# Triac.net
KiCad netlist of a schematic drawn in Altium Designer
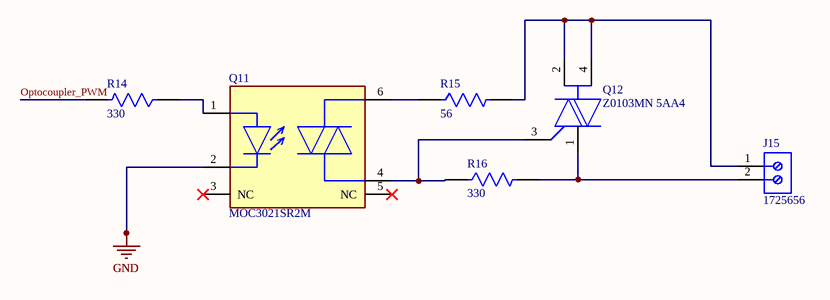
[diagram p0: Triac.SchDoc]

(export (version "E")
  (design (tool "Eeschema 10.0.6"))
  (components
    (comp (ref "J15")
      (value "1725656")
      (footprint "PHOE-1725656-2")
      (description "Male Header, Pitch 2.54 mm, 1 x 2 Position, Height 9 mm, Tail Length 3.5 mm")
      (fields (field (name "MANUFACTURER") "Phoenix Contact"))
      (libsource (lib "Altium Content Vault") (part "CN-1P-F-TB2"))
    )
    (comp (ref "Q11")
      (value "MOC3021SR2M")
      (footprint "FP-646BY-MFG")
      (description "MOC3021SR2M Triac Driver Output Optocoupler, 6-Pin DIP 400V Random Phase")
      (libsource (lib "Altium Content Vault") (part "ac99fbad1a7223516b687fb475d83a7"))
    )
    (comp (ref "Q12")
      (value "Z0103MN 5AA4")
      (footprint "FP-SOT-223-MFG")
      (description "TRIAC SENS GATE 600V 1A SOT223")
      (libsource (lib "Altium Content Vault") (part "0451cdb22eca37168295a7e46b27c2f"))
    )
    (comp (ref "R14")
      (value "MCA1206MD1002DP500")
      (footprint "FP-MCA1206-IPC_B")
      (description "Res MC AT Professional Thin Film 1206 10kΩ 0.5% 0.4W ±25ppm/°C Molded Paper T/R")
      (fields (field (name "RESISTANCE") "330") (field (name "TOLERANCE") "0.5%"))
      (libsource (lib "Altium Content Vault") (part "1029c3af85768c4190bb7ad29bc67b5"))
    )
    (comp (ref "R15")
      (value "MCA1206MD1002DP500")
      (footprint "FP-MCA1206-IPC_B")
      (description "Res MC AT Professional Thin Film 1206 10kΩ 0.5% 0.4W ±25ppm/°C Molded Paper T/R")
      (fields (field (name "RESISTANCE") "56") (field (name "TOLERANCE") "0.5%"))
      (libsource (lib "Altium Content Vault") (part "1029c3af85768c4190bb7ad29bc67b5"))
    )
    (comp (ref "R16")
      (value "MCA1206MD1002DP500")
      (footprint "FP-MCA1206-IPC_B")
      (description "Res MC AT Professional Thin Film 1206 10kΩ 0.5% 0.4W ±25ppm/°C Molded Paper T/R")
      (fields (field (name "RESISTANCE") "330") (field (name "TOLERANCE") "0.5%"))
      (libsource (lib "Altium Content Vault") (part "1029c3af85768c4190bb7ad29bc67b5"))
    )
  )
  (nets
    (net (code "1") (name "/Optocoupler_PWM") (class "Default")
      (node (ref "R14") (pin "2") (pinfunction "2_2") (pintype "passive"))
    )
    (net (code "2") (name "GND") (class "Default")
      (node (ref "Q11") (pin "2") (pinfunction "C_2") (pintype "passive"))
    )
    (net (code "3") (name "Net-(J15-Pad1)") (class "Default")
      (node (ref "J15") (pin "1") (pinfunction "1_1") (pintype "passive"))
      (node (ref "Q12") (pin "2") (pinfunction "A2_2") (pintype "passive"))
      (node (ref "Q12") (pin "4") (pinfunction "A2_4") (pintype "passive"))
      (node (ref "R15") (pin "2") (pinfunction "2_2") (pintype "passive"))
    )
    (net (code "4") (name "Net-(Q11-1_MAIN_TERM.)") (class "Default")
      (node (ref "Q11") (pin "4") (pinfunction "1_MAIN_TERM._4") (pintype "passive"))
      (node (ref "Q12") (pin "3") (pinfunction "G_3") (pintype "passive"))
      (node (ref "R16") (pin "1") (pinfunction "1_1") (pintype "passive"))
    )
    (net (code "5") (name "Net-(Q11-2_MAIN_TERM.)") (class "Default")
      (node (ref "Q11") (pin "6") (pinfunction "2_MAIN_TERM._6") (pintype "passive"))
      (node (ref "R15") (pin "1") (pinfunction "1_1") (pintype "passive"))
    )
    (net (code "6") (name "Net-(Q11-A)") (class "Default")
      (node (ref "Q11") (pin "1") (pinfunction "A_1") (pintype "passive"))
      (node (ref "R14") (pin "1") (pinfunction "1_1") (pintype "passive"))
    )
    (net (code "7") (name "Net-(Q12-A1)") (class "Default")
      (node (ref "J15") (pin "2") (pinfunction "2_2") (pintype "passive"))
      (node (ref "Q12") (pin "1") (pinfunction "A1_1") (pintype "passive"))
      (node (ref "R16") (pin "2") (pinfunction "2_2") (pintype "passive"))
    )
    (net (code "8") (name "unconnected-(Q11-NC-Pad3)") (class "Default")
      (node (ref "Q11") (pin "3") (pinfunction "NC_3") (pintype "passive+no_connect"))
    )
    (net (code "9") (name "unconnected-(Q11-NC-Pad5)") (class "Default")
      (node (ref "Q11") (pin "5") (pinfunction "NC_5") (pintype "passive+no_connect"))
    )
  )
)
